# CTR_UVOV.net
KiCad netlist of a schematic drawn in Altium Designer
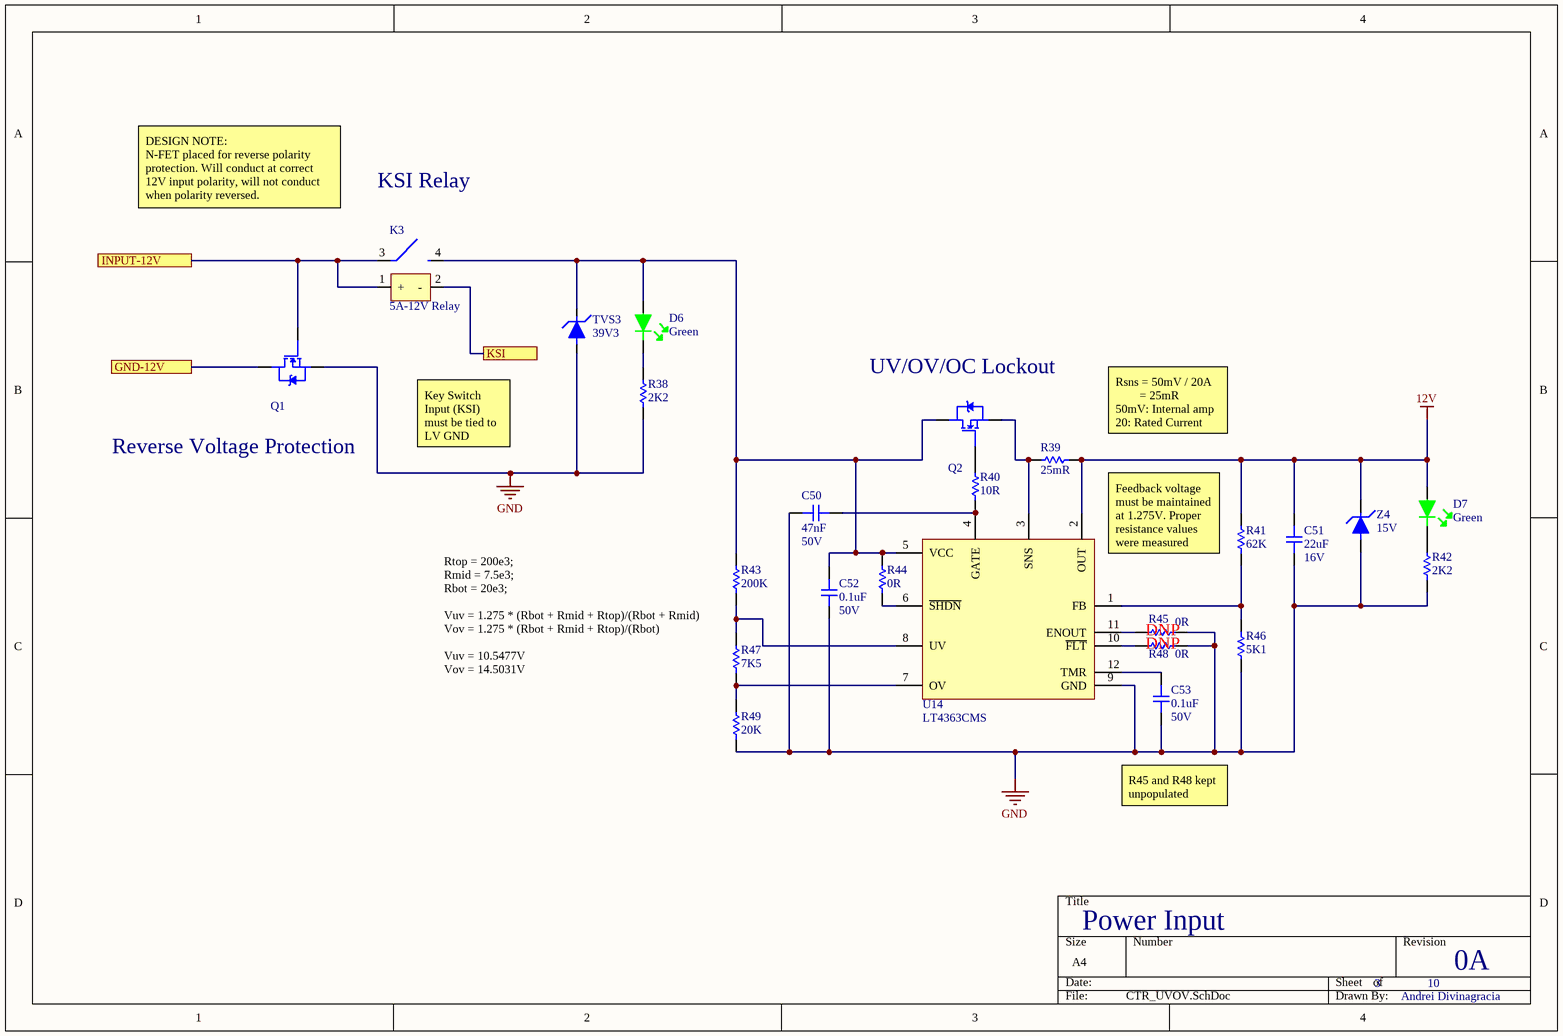
[diagram p0: CTR_UVOV.SchDoc]

(export (version "E")
  (design (tool "Eeschema 10.0.6"))
  (components
    (comp (ref "C50")
      (value "47nF")
      (footprint "CAP-0805")
      (description "CAP CER 0.047UF 50V X7R 0805")
      (fields
        (field (name "MANUFACTURER") "Yageo")
        (field (name "MANUFACTURER PART NUMBER") "CC0805KRX7R9BB473")
        (field (name "VOLTAGE") "50V")
      )
      (libsource (lib "InverterSCHLib") (part "0805-47nF-50V"))
    )
    (comp (ref "C51")
      (value "22uF")
      (footprint "CAP-0805")
      (description "CAP CER 22UF 16V X5R 0805")
      (fields
        (field (name "MANUFACTURER") "Samsung")
        (field (name "MANUFACTURER PART NUMBER") "CL21A226KOQNNNE")
        (field (name "VOLTAGE RATING") "16V")
      )
      (libsource (lib "InverterSCHLib") (part "CL21A226KOQNNNE"))
    )
    (comp (ref "C52")
      (value "0.1uF")
      (footprint "CAP-0603")
      (description "CAP CER 0.1UF 50V X7R 0603")
      (fields
        (field (name "MANUFACTURER") "Samsung")
        (field (name "MANUFACTURER PART NUMBER") "CL10B104KB8NNNL")
        (field (name "VOLTAGE RATING") "50V")
      )
      (libsource (lib "InverterSCHLib") (part "0603-0.1uF-50V"))
    )
    (comp (ref "C53")
      (value "0.1uF")
      (footprint "CAP-0603")
      (description "CAP CER 0.1UF 50V X7R 0603")
      (fields
        (field (name "MANUFACTURER") "Samsung")
        (field (name "MANUFACTURER PART NUMBER") "CL10B104KB8NNNL")
        (field (name "VOLTAGE RATING") "50V")
      )
      (libsource (lib "InverterSCHLib") (part "0603-0.1uF-50V"))
    )
    (comp (ref "D6")
      (value "Green")
      (footprint "LED-0603")
      (description "LED GREEN CLEAR 0603 SMD")
      (fields
        (field (name "MANUFACTURER") "Wurth Electronics")
        (field (name "MANUFACTURER PART NUMBER") "150060VS75000")
      )
      (libsource (lib "InverterSCHLib") (part "LED-Green"))
    )
    (comp (ref "D7")
      (value "Green")
      (footprint "LED-0603")
      (description "LED GREEN CLEAR 0603 SMD")
      (fields
        (field (name "MANUFACTURER") "Wurth Electronics")
        (field (name "MANUFACTURER PART NUMBER") "150060VS75000")
      )
      (libsource (lib "InverterSCHLib") (part "LED-Green"))
    )
    (comp (ref "K3")
      (value "5A-12V Relay")
      (footprint "Relay")
      (description "General Purpose Relay SPST-NO (1 Form A) 12VDC Coil Through Hole")
      (fields
        (field (name "MANUFACTURER") "TE Connectivity")
        (field (name "MANUFACTURER PART NUMBER") "OJE-SH-112DM,000")
      )
      (libsource (lib "InverterSCHLib") (part "OJE-SH-112DM,000"))
    )
    (comp (ref "Q1")
      (value "DMN6040SK3-13")
      (footprint "TO-252-3")
      (description "MOSFET N CH 60V 20A TO252")
      (fields (field (name "MANUFACTURER") "Diodes"))
      (libsource (lib "InverterSCHLib") (part "DMN6040SK3-13"))
    )
    (comp (ref "Q2")
      (value "DMN6040SK3-13")
      (footprint "TO-252-3")
      (description "MOSFET N CH 60V 20A TO252")
      (fields (field (name "MANUFACTURER") "Diodes"))
      (libsource (lib "InverterSCHLib") (part "DMN6040SK3-13"))
    )
    (comp (ref "R38")
      (value "2K2")
      (footprint "RES-0603")
      (description "RES SMD 2.2K OHM 5% 1/10W 0603")
      (fields
        (field (name "MANUFACTURER") "Yageo")
        (field (name "MANUFACTURER PART NUMBER") "AC0603JR-072K2L")
      )
      (libsource (lib "InverterSCHLib") (part "0603-2K2"))
    )
    (comp (ref "R39")
      (value "25mR")
      (footprint "RES-2512")
      (description "RES SMD 25 MOHM 1% 2W 2512")
      (fields
        (field (name "MANUFACTURER") "Riedon")
        (field (name "MANUFACTURER PART NUMBER") "CSR2512A0R025F")
      )
      (libsource (lib "InverterSCHLib") (part "2512-25mR-SHUNT"))
    )
    (comp (ref "R40")
      (value "10R")
      (footprint "RES-0603")
      (description "RES SMD 10 OHM 1% 1/10W 0603")
      (fields
        (field (name "MANUFACTURER") "Yageo")
        (field (name "MANUFACTURER PART NUMBER") "RC0603FR-0710RL")
      )
      (libsource (lib "InverterSCHLib") (part "0603-10R"))
    )
    (comp (ref "R41")
      (value "62K")
      (footprint "RES-0603")
      (description "RES SMD 62K OHM 1% 1/4W 0603")
      (fields
        (field (name "MANUFACTURER") "Panasonic")
        (field (name "MANUFACTURER PART NUMBER") "ERJ-PA3F6202V")
      )
      (libsource (lib "InverterSCHLib") (part "0603-62K"))
    )
    (comp (ref "R42")
      (value "2K2")
      (footprint "RES-0603")
      (description "RES SMD 2.2K OHM 5% 1/10W 0603")
      (fields
        (field (name "MANUFACTURER") "Yageo")
        (field (name "MANUFACTURER PART NUMBER") "AC0603JR-072K2L")
      )
      (libsource (lib "InverterSCHLib") (part "0603-2K2"))
    )
    (comp (ref "R43")
      (value "200K")
      (footprint "RES-0603")
      (description "RES SMD 200K OHM 1% 1/10W 0603")
      (fields
        (field (name "MANUFACTURER") "Yageo")
        (field (name "MANUFACTURER PART NUMBER") "AF0603FR-07200KL")
      )
      (libsource (lib "InverterSCHLib") (part "0603-200KR"))
    )
    (comp (ref "R44")
      (value "0R")
      (footprint "RES-0603")
      (description "RES SMD 0 OHM JUMPER 1/10W 0603")
      (fields
        (field (name "MANUFACTURER") "Yageo")
        (field (name "MANUFACTURER PART NUMBER") "RC0603JR-070RL")
      )
      (libsource (lib "InverterSCHLib") (part "0603-0R"))
    )
    (comp (ref "R45")
      (value "0R")
      (footprint "RES-0603")
      (description "RES SMD 0 OHM JUMPER 1/10W 0603")
      (fields
        (field (name "MANUFACTURER") "Yageo")
        (field (name "MANUFACTURER PART NUMBER") "RC0603JR-070RL")
      )
      (libsource (lib "InverterSCHLib") (part "0603-0R"))
    )
    (comp (ref "R46")
      (value "5K1")
      (footprint "RES-0603")
      (description "RES SMD 5.1K OHM 1% 1/10W 0603")
      (fields
        (field (name "MANUFACTURER") "TE Connectivity")
        (field (name "MANUFACTURER PART NUMBER") "1623257-1")
      )
      (libsource (lib "InverterSCHLib") (part "0603-5.1KR"))
    )
    (comp (ref "R47")
      (value "7K5")
      (footprint "RES-0603")
      (description "RES SMD 7.5K OHM 5% 1/10W 0603")
      (fields
        (field (name "MANUFACTURER") "Yageo")
        (field (name "MANUFACTURER PART NUMBER") "RC0603JR-077K5L")
      )
      (libsource (lib "InverterSCHLib") (part "0603-7K5"))
    )
    (comp (ref "R48")
      (value "0R")
      (footprint "RES-0603")
      (description "RES SMD 0 OHM JUMPER 1/10W 0603")
      (fields
        (field (name "MANUFACTURER") "Yageo")
        (field (name "MANUFACTURER PART NUMBER") "RC0603JR-070RL")
      )
      (libsource (lib "InverterSCHLib") (part "0603-0R"))
    )
    (comp (ref "R49")
      (value "20K")
      (footprint "RES-0603")
      (description "RES SMD 20K OHM 5% 1/10W 0603")
      (fields
        (field (name "MANUFACTURER") "Yageo")
        (field (name "MANUFACTURER PART NUMBER") "RC0603JR-0720KL")
      )
      (libsource (lib "InverterSCHLib") (part "0603-20K"))
    )
    (comp (ref "TVS3")
      (value "39V3")
      (footprint "DO-214AC")
      (description "TVS DIODE 18VWM 39.3VC SMA")
      (fields
        (field (name "MANUFACTURER") "STMicroelectronics")
        (field (name "MANUFACTURER PART NUMBER") "SMAJ18CA-TR")
      )
      (libsource (lib "InverterSCHLib") (part "SMAJ18CA-TR-Bi"))
    )
    (comp (ref "U14")
      (value "LT4363CMS")
      (footprint "SSOP12-UVOV")
      (description "IC SURGE STOPPER HV 12-MSOP")
      (fields
        (field (name "MANUFACTURER") "Analog Devices / Linear Technology")
        (field (name "MANUFACTURER PART NUMBER") "LT4363CMS-2#PBF")
      )
      (libsource (lib "InverterSCHLib") (part "LT4363CMS-2#PBF"))
    )
    (comp (ref "Z4")
      (value "15V")
      (footprint "DO-214AC")
      (description "Diode Zener Single 15V 5% 500mW 2-Pin SMA T/R")
      (fields
        (field (name "MANUFACTURER") "ON Semiconductor")
        (field (name "MANUFACTURER PART NUMBER") "1SMA5929BT3G")
      )
      (libsource (lib "InverterSCHLib") (part "1SMA5929BT3G"))
    )
  )
  (nets
    (net (code "1") (name "/GND-12V") (class "Default")
      (node (ref "Q1") (pin "2") (pinfunction "D_2") (pintype "passive"))
    )
    (net (code "2") (name "/INPUT-12V") (class "Default")
      (node (ref "K3") (pin "1") (pinfunction "+_1") (pintype "passive"))
      (node (ref "K3") (pin "3") (pinfunction "3_3") (pintype "passive"))
      (node (ref "Q1") (pin "1") (pinfunction "G_1") (pintype "passive"))
    )
    (net (code "3") (name "/KSI") (class "Default")
      (node (ref "K3") (pin "2") (pinfunction "-_2") (pintype "passive"))
    )
    (net (code "4") (name "12V") (class "Default")
      (node (ref "C51") (pin "2") (pinfunction "2_2") (pintype "passive"))
      (node (ref "D7") (pin "1") (pinfunction "1_1") (pintype "passive"))
      (node (ref "R39") (pin "1") (pinfunction "1_1") (pintype "passive"))
      (node (ref "R41") (pin "2") (pinfunction "2_2") (pintype "passive"))
      (node (ref "U14") (pin "2") (pinfunction "OUT_2") (pintype "passive"))
      (node (ref "Z4") (pin "1") (pinfunction "1_1") (pintype "passive"))
    )
    (net (code "5") (name "GND") (class "Default")
      (node (ref "C50") (pin "1") (pinfunction "1_1") (pintype "passive"))
      (node (ref "C51") (pin "1") (pinfunction "1_1") (pintype "passive"))
      (node (ref "C52") (pin "1") (pinfunction "1_1") (pintype "passive"))
      (node (ref "C53") (pin "1") (pinfunction "1_1") (pintype "passive"))
      (node (ref "Q1") (pin "3") (pinfunction "S_3") (pintype "passive"))
      (node (ref "R38") (pin "1") (pinfunction "1_1") (pintype "passive"))
      (node (ref "R42") (pin "1") (pinfunction "1_1") (pintype "passive"))
      (node (ref "R45") (pin "1") (pinfunction "1_1") (pintype "passive"))
      (node (ref "R46") (pin "2") (pinfunction "2_2") (pintype "passive"))
      (node (ref "R48") (pin "1") (pinfunction "1_1") (pintype "passive"))
      (node (ref "R49") (pin "1") (pinfunction "1_1") (pintype "passive"))
      (node (ref "TVS3") (pin "2") (pinfunction "2_2") (pintype "passive"))
      (node (ref "U14") (pin "9") (pinfunction "GND_9") (pintype "passive"))
      (node (ref "Z4") (pin "2") (pinfunction "2_2") (pintype "passive"))
    )
    (net (code "6") (name "Net-(D6-Pad2)") (class "Default")
      (node (ref "D6") (pin "2") (pinfunction "2_2") (pintype "passive"))
      (node (ref "R38") (pin "2") (pinfunction "2_2") (pintype "passive"))
    )
    (net (code "7") (name "Net-(D7-Pad2)") (class "Default")
      (node (ref "D7") (pin "2") (pinfunction "2_2") (pintype "passive"))
      (node (ref "R42") (pin "2") (pinfunction "2_2") (pintype "passive"))
    )
    (net (code "8") (name "Net-(Q2-D)") (class "Default")
      (node (ref "C52") (pin "2") (pinfunction "2_2") (pintype "passive"))
      (node (ref "D6") (pin "1") (pinfunction "1_1") (pintype "passive"))
      (node (ref "K3") (pin "4") (pinfunction "4_4") (pintype "passive"))
      (node (ref "Q2") (pin "2") (pinfunction "D_2") (pintype "passive"))
      (node (ref "R43") (pin "2") (pinfunction "2_2") (pintype "passive"))
      (node (ref "R44") (pin "2") (pinfunction "2_2") (pintype "passive"))
      (node (ref "TVS3") (pin "1") (pinfunction "1_1") (pintype "passive"))
      (node (ref "U14") (pin "5") (pinfunction "VCC_5") (pintype "passive"))
    )
    (net (code "9") (name "Net-(Q2-G)") (class "Default")
      (node (ref "Q2") (pin "1") (pinfunction "G_1") (pintype "passive"))
      (node (ref "R40") (pin "2") (pinfunction "2_2") (pintype "passive"))
    )
    (net (code "10") (name "Net-(Q2-S)") (class "Default")
      (node (ref "Q2") (pin "3") (pinfunction "S_3") (pintype "passive"))
      (node (ref "R39") (pin "2") (pinfunction "2_2") (pintype "passive"))
      (node (ref "U14") (pin "3") (pinfunction "SNS_3") (pintype "passive"))
    )
    (net (code "11") (name "Net-(U14-ENOUT)") (class "Default")
      (node (ref "R45") (pin "2") (pinfunction "2_2") (pintype "passive"))
      (node (ref "U14") (pin "11") (pinfunction "ENOUT_11") (pintype "passive"))
    )
    (net (code "12") (name "Net-(U14-FB)") (class "Default")
      (node (ref "R41") (pin "1") (pinfunction "1_1") (pintype "passive"))
      (node (ref "R46") (pin "1") (pinfunction "1_1") (pintype "passive"))
      (node (ref "U14") (pin "1") (pinfunction "FB_1") (pintype "passive"))
    )
    (net (code "13") (name "Net-(U14-GATE)") (class "Default")
      (node (ref "C50") (pin "2") (pinfunction "2_2") (pintype "passive"))
      (node (ref "R40") (pin "1") (pinfunction "1_1") (pintype "passive"))
      (node (ref "U14") (pin "4") (pinfunction "GATE_4") (pintype "passive"))
    )
    (net (code "14") (name "Net-(U14-OV)") (class "Default")
      (node (ref "R47") (pin "1") (pinfunction "1_1") (pintype "passive"))
      (node (ref "R49") (pin "2") (pinfunction "2_2") (pintype "passive"))
      (node (ref "U14") (pin "7") (pinfunction "OV_7") (pintype "passive"))
    )
    (net (code "15") (name "Net-(U14-TMR)") (class "Default")
      (node (ref "C53") (pin "2") (pinfunction "2_2") (pintype "passive"))
      (node (ref "U14") (pin "12") (pinfunction "TMR_12") (pintype "passive"))
    )
    (net (code "16") (name "Net-(U14-UV)") (class "Default")
      (node (ref "R43") (pin "1") (pinfunction "1_1") (pintype "passive"))
      (node (ref "R47") (pin "2") (pinfunction "2_2") (pintype "passive"))
      (node (ref "U14") (pin "8") (pinfunction "UV_8") (pintype "passive"))
    )
    (net (code "17") (name "Net-(U14-~{FLT})") (class "Default")
      (node (ref "R48") (pin "2") (pinfunction "2_2") (pintype "passive"))
      (node (ref "U14") (pin "10") (pinfunction "~{FLT}_10") (pintype "passive"))
    )
    (net (code "18") (name "Net-(U14-~{SHDN})") (class "Default")
      (node (ref "R44") (pin "1") (pinfunction "1_1") (pintype "passive"))
      (node (ref "U14") (pin "6") (pinfunction "~{SHDN}_6") (pintype "passive"))
    )
  )
)
